# Pt100-Amplifier-LM324-2.net
KiCad netlist of a schematic drawn in EAGLE
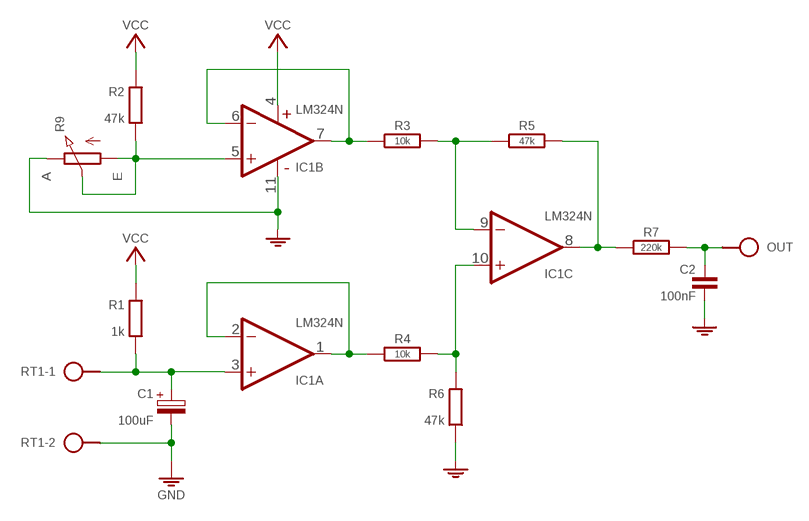
[diagram p0: schematic, sheet 1]

(export (version "E")
  (design (tool "Eeschema 10.0.6"))
  (components
    (comp (ref "C1")
      (value "100uF")
      (footprint "eagle-import:E2,5-6")
      (libsource (lib "eagle-import") (part "CPOLE2.5-6"))
    )
    (comp (ref "C2")
      (value "100nF")
      (footprint "eagle-import:C050-020X044_V")
      (libsource (lib "eagle-import") (part "C050-020X044/V"))
    )
    (comp (ref "IC1")
      (value "LM324N")
      (footprint "eagle-import:DIL14")
      (libsource (lib "eagle-import") (part "LM324N"))
    )
    (comp (ref "OUT")
      (value "HPORT")
      (footprint "eagle-import:SPAD")
      (libsource (lib "eagle-import") (part "HPORT"))
    )
    (comp (ref "R1")
      (value "1k")
      (footprint "eagle-import:0204_2.54")
      (libsource (lib "eagle-import") (part "R0204/2.54"))
    )
    (comp (ref "R2")
      (value "47k")
      (footprint "eagle-import:0204_2.54")
      (libsource (lib "eagle-import") (part "R0204/2.54"))
    )
    (comp (ref "R3")
      (value "10k")
      (footprint "eagle-import:0204_10")
      (libsource (lib "eagle-import") (part "R-H0204/10"))
    )
    (comp (ref "R4")
      (value "10k")
      (footprint "eagle-import:0204_12")
      (libsource (lib "eagle-import") (part "R-H0204/12"))
    )
    (comp (ref "R5")
      (value "47k")
      (footprint "eagle-import:0204_2.54")
      (libsource (lib "eagle-import") (part "R-H0204/2.54"))
    )
    (comp (ref "R6")
      (value "47k")
      (footprint "eagle-import:0204_2.54")
      (libsource (lib "eagle-import") (part "R0204/2.54"))
    )
    (comp (ref "R7")
      (value "220k")
      (footprint "eagle-import:0204_10")
      (libsource (lib "eagle-import") (part "R-H0204/10"))
    )
    (comp (ref "R9")
      (value "POT-TRIM")
      (footprint "eagle-import:TRIM-POT")
      (libsource (lib "eagle-import") (part "POT-TRIM"))
    )
    (comp (ref "RT1")
      (value "SPAD-2")
      (footprint "eagle-import:SPAD-2")
      (libsource (lib "eagle-import") (part "SPAD-2"))
    )
    (comp (ref "S5")
      (value "VCC_GNDPWR-L")
      (footprint "eagle-import:PWR-L")
      (libsource (lib "eagle-import") (part "VCC_GNDPWR-L"))
    )
  )
  (nets
    (net (code "1") (name "GND") (class "Default")
      (node (ref "C1") (pin "-") (pinfunction "-_-") (pintype "passive"))
      (node (ref "C2") (pin "2") (pinfunction "2_2") (pintype "passive"))
      (node (ref "IC1") (pin "11") (pinfunction "V-_11") (pintype "power_in"))
      (node (ref "R6") (pin "2") (pinfunction "1_2") (pintype "passive"))
      (node (ref "R9") (pin "E") (pinfunction "E_E") (pintype "passive"))
      (node (ref "RT1") (pin "2") (pinfunction "P$1_2") (pintype "passive"))
      (node (ref "S5") (pin "1") (pinfunction "GND_1") (pintype "power_in"))
    )
    (net (code "2") (name "Net-(IC1A-+IN)") (class "Default")
      (node (ref "C1") (pin "+") (pinfunction "+_+") (pintype "passive"))
      (node (ref "IC1") (pin "3") (pinfunction "+IN_3") (pintype "input"))
      (node (ref "R1") (pin "2") (pinfunction "1_2") (pintype "passive"))
      (node (ref "RT1") (pin "1") (pinfunction "P$1_1") (pintype "passive"))
    )
    (net (code "3") (name "Net-(IC1A--IN)") (class "Default")
      (node (ref "IC1") (pin "1") (pinfunction "OUT_1") (pintype "output"))
      (node (ref "IC1") (pin "2") (pinfunction "-IN_2") (pintype "input"))
      (node (ref "R4") (pin "1") (pinfunction "1_1") (pintype "passive"))
    )
    (net (code "4") (name "Net-(IC1B-+IN)") (class "Default")
      (node (ref "IC1") (pin "5") (pinfunction "+IN_5") (pintype "input"))
      (node (ref "R2") (pin "2") (pinfunction "1_2") (pintype "passive"))
      (node (ref "R9") (pin "A") (pinfunction "A_A") (pintype "passive"))
      (node (ref "R9") (pin "S") (pinfunction "S_S") (pintype "passive"))
    )
    (net (code "5") (name "Net-(IC1B--IN)") (class "Default")
      (node (ref "IC1") (pin "6") (pinfunction "-IN_6") (pintype "input"))
      (node (ref "IC1") (pin "7") (pinfunction "OUT_7") (pintype "output"))
      (node (ref "R3") (pin "1") (pinfunction "1_1") (pintype "passive"))
    )
    (net (code "6") (name "Net-(IC1C-+IN)") (class "Default")
      (node (ref "IC1") (pin "10") (pinfunction "+IN_10") (pintype "input"))
      (node (ref "R4") (pin "2") (pinfunction "2_2") (pintype "passive"))
      (node (ref "R6") (pin "1") (pinfunction "2_1") (pintype "passive"))
    )
    (net (code "7") (name "Net-(IC1C--IN)") (class "Default")
      (node (ref "IC1") (pin "9") (pinfunction "-IN_9") (pintype "input"))
      (node (ref "R3") (pin "2") (pinfunction "2_2") (pintype "passive"))
      (node (ref "R5") (pin "1") (pinfunction "1_1") (pintype "passive"))
    )
    (net (code "8") (name "Net-(IC1C-OUT)") (class "Default")
      (node (ref "IC1") (pin "8") (pinfunction "OUT_8") (pintype "output"))
      (node (ref "R5") (pin "2") (pinfunction "2_2") (pintype "passive"))
      (node (ref "R7") (pin "1") (pinfunction "1_1") (pintype "passive"))
    )
    (net (code "9") (name "Net-(OUT-P$1)") (class "Default")
      (node (ref "C2") (pin "1") (pinfunction "1_1") (pintype "passive"))
      (node (ref "OUT") (pin "1") (pinfunction "P$1_1") (pintype "passive"))
      (node (ref "R7") (pin "2") (pinfunction "2_2") (pintype "passive"))
    )
    (net (code "10") (name "VCC") (class "Default")
      (node (ref "IC1") (pin "4") (pinfunction "V+_4") (pintype "power_in"))
      (node (ref "R1") (pin "1") (pinfunction "2_1") (pintype "passive"))
      (node (ref "R2") (pin "1") (pinfunction "2_1") (pintype "passive"))
      (node (ref "S5") (pin "2") (pinfunction "VCC_2") (pintype "power_in"))
    )
  )
)
